# potbot_v6.net
KiCad netlist of a schematic drawn in EAGLE
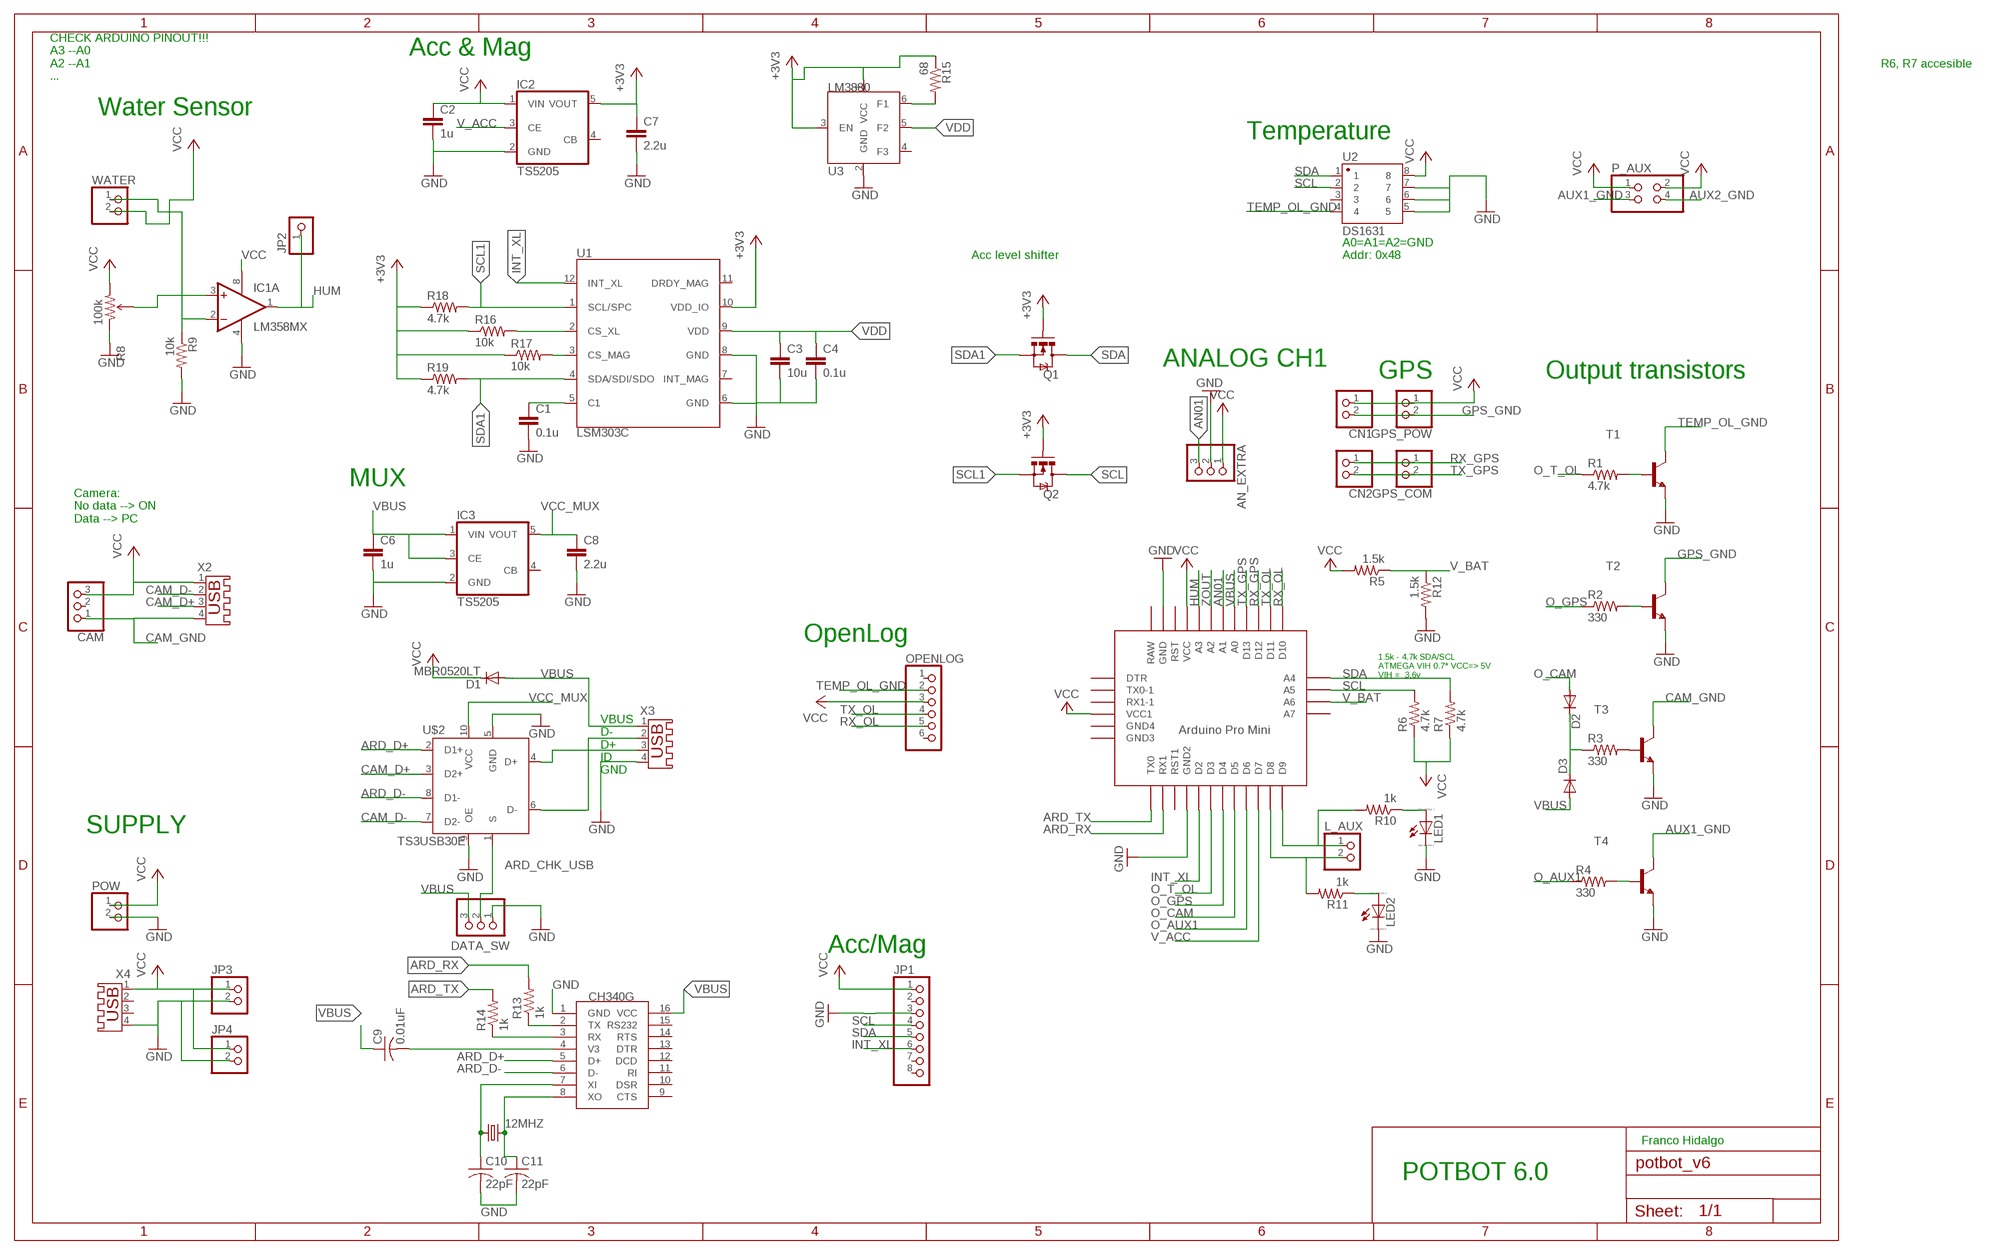
[diagram p0: schematic, sheet 1]

(export (version "E")
  (design (tool "Eeschema 10.0.6"))
  (components
    (comp (ref "12MHZ")
      (value "CRYSTALSM49")
      (footprint "eagle-import:SM49")
      (libsource (lib "eagle-import") (part "CRYSTALSM49"))
    )
    (comp (ref "AN_EXTRA")
      (value "PINHD-1X3")
      (footprint "eagle-import:1X03")
      (libsource (lib "eagle-import") (part "PINHD-1X3"))
    )
    (comp (ref "ARDUINO")
      (value "PRO-MINI-2")
      (footprint "eagle-import:PRO-MINI-2")
      (libsource (lib "eagle-import") (part "PRO-MINI-2"))
    )
    (comp (ref "C1")
      (value "0.1u")
      (footprint "eagle-import:C1206")
      (libsource (lib "eagle-import") (part "C-EUC1206"))
    )
    (comp (ref "C2")
      (value "1u")
      (footprint "eagle-import:C1206")
      (libsource (lib "eagle-import") (part "C-EUC1206"))
    )
    (comp (ref "C3")
      (value "10u")
      (footprint "eagle-import:C1206")
      (libsource (lib "eagle-import") (part "C-EUC1206"))
    )
    (comp (ref "C4")
      (value "0.1u")
      (footprint "eagle-import:C1206")
      (libsource (lib "eagle-import") (part "C-EUC1206"))
    )
    (comp (ref "C6")
      (value "1u")
      (footprint "eagle-import:C1206")
      (libsource (lib "eagle-import") (part "C-EUC1206"))
    )
    (comp (ref "C7")
      (value "2.2u")
      (footprint "eagle-import:C1206")
      (libsource (lib "eagle-import") (part "C-EUC1206"))
    )
    (comp (ref "C8")
      (value "2.2u")
      (footprint "eagle-import:C1206")
      (libsource (lib "eagle-import") (part "C-EUC1206"))
    )
    (comp (ref "C9")
      (value "0.01uF")
      (footprint "eagle-import:C1206")
      (libsource (lib "eagle-import") (part "C-USC1206"))
    )
    (comp (ref "C10")
      (value "22pF")
      (footprint "eagle-import:C1206")
      (libsource (lib "eagle-import") (part "C-USC1206"))
    )
    (comp (ref "C11")
      (value "22pF")
      (footprint "eagle-import:C1206")
      (libsource (lib "eagle-import") (part "C-USC1206"))
    )
    (comp (ref "CAM")
      (value "PINHD-1X3")
      (footprint "eagle-import:1X03")
      (libsource (lib "eagle-import") (part "pinhead_PINHD-1X3"))
    )
    (comp (ref "CN1")
      (value "JST_2PIN-THM")
      (footprint "eagle-import:JST-PH-2-THM")
      (libsource (lib "eagle-import") (part "JST_2PIN-THM"))
    )
    (comp (ref "CN2")
      (value "JST_2PIN-THM")
      (footprint "eagle-import:JST-PH-2-THM")
      (libsource (lib "eagle-import") (part "JST_2PIN-THM"))
    )
    (comp (ref "D1")
      (value "MBR0520LT")
      (footprint "eagle-import:SOD123")
      (libsource (lib "eagle-import") (part "MBR0520LT"))
    )
    (comp (ref "D2")
      (value "MBR0520LT")
      (footprint "eagle-import:SOD123")
      (libsource (lib "eagle-import") (part "MBR0520LT"))
    )
    (comp (ref "D3")
      (value "MBR0520LT")
      (footprint "eagle-import:SOD123")
      (libsource (lib "eagle-import") (part "MBR0520LT"))
    )
    (comp (ref "DATA_SW")
      (value "PINHD-1X3")
      (footprint "eagle-import:1X03")
      (libsource (lib "eagle-import") (part "pinhead_PINHD-1X3"))
    )
    (comp (ref "GPS_COM")
      (value "JST_2PIN-SMT")
      (footprint "eagle-import:JST-PH-2-SMT")
      (libsource (lib "eagle-import") (part "JST_2PIN-SMT"))
    )
    (comp (ref "GPS_POW")
      (value "JST_2PIN-SMT")
      (footprint "eagle-import:JST-PH-2-SMT")
      (libsource (lib "eagle-import") (part "JST_2PIN-SMT"))
    )
    (comp (ref "IC1")
      (value "LM358MX")
      (footprint "eagle-import:SO08")
      (libsource (lib "eagle-import") (part "LM358MX"))
    )
    (comp (ref "IC2")
      (value "TS5205")
      (footprint "eagle-import:SOT25")
      (libsource (lib "eagle-import") (part "TS5205"))
    )
    (comp (ref "IC3")
      (value "TS5205")
      (footprint "eagle-import:SOT25")
      (libsource (lib "eagle-import") (part "TS5205"))
    )
    (comp (ref "JP1")
      (value "PINHD-1X8CLEANBIG")
      (footprint "eagle-import:1X08-CLEANBIG")
      (libsource (lib "eagle-import") (part "PINHD-1X8CLEANBIG"))
    )
    (comp (ref "JP2")
      (value "PINHD-1X1")
      (footprint "eagle-import:1X01")
      (libsource (lib "eagle-import") (part "PINHD-1X1"))
    )
    (comp (ref "JP3")
      (value "PINHD-1X2")
      (footprint "eagle-import:1X02")
      (libsource (lib "eagle-import") (part "PINHD-1X2"))
    )
    (comp (ref "JP4")
      (value "PINHD-1X2")
      (footprint "eagle-import:1X02")
      (libsource (lib "eagle-import") (part "PINHD-1X2"))
    )
    (comp (ref "LED1")
      (value "LED_ELD260")
      (footprint "eagle-import:LED_LD260")
      (libsource (lib "eagle-import") (part "LED_ELD260"))
    )
    (comp (ref "LED2")
      (value "LED_ELD260")
      (footprint "eagle-import:LED_LD260")
      (libsource (lib "eagle-import") (part "LED_ELD260"))
    )
    (comp (ref "L_AUX")
      (value "PINHD-1X2")
      (footprint "eagle-import:1X02")
      (libsource (lib "eagle-import") (part "PINHD-1X2"))
    )
    (comp (ref "OPENLOG")
      (value "PINHD-1X6")
      (footprint "eagle-import:1X06")
      (libsource (lib "eagle-import") (part "PINHD-1X6"))
    )
    (comp (ref "POW")
      (value "PINHD-1X2")
      (footprint "eagle-import:1X02")
      (libsource (lib "eagle-import") (part "PINHD-1X2"))
    )
    (comp (ref "P_AUX")
      (value "PINHD-2X2")
      (footprint "eagle-import:2X02")
      (libsource (lib "eagle-import") (part "PINHD-2X2"))
    )
    (comp (ref "Q1")
      (value "MOSFET-NCHANNELAO3404A")
      (footprint "eagle-import:SOT23-3")
      (libsource (lib "eagle-import") (part "MOSFET-NCHANNELAO3404A"))
    )
    (comp (ref "Q2")
      (value "MOSFET-NCHANNELAO3404A")
      (footprint "eagle-import:SOT23-3")
      (libsource (lib "eagle-import") (part "MOSFET-NCHANNELAO3404A"))
    )
    (comp (ref "R1")
      (value "4.7k")
      (footprint "eagle-import:M1206")
      (libsource (lib "eagle-import") (part "R-US_M1206"))
    )
    (comp (ref "R2")
      (value "330")
      (footprint "eagle-import:M1206")
      (libsource (lib "eagle-import") (part "R-US_M1206"))
    )
    (comp (ref "R3")
      (value "330")
      (footprint "eagle-import:M1206")
      (libsource (lib "eagle-import") (part "R-US_M1206"))
    )
    (comp (ref "R4")
      (value "330")
      (footprint "eagle-import:M1206")
      (libsource (lib "eagle-import") (part "R-US_M1206"))
    )
    (comp (ref "R5")
      (value "1.5k")
      (footprint "eagle-import:M1206")
      (libsource (lib "eagle-import") (part "R-US_M1206"))
    )
    (comp (ref "R6")
      (value "4.7k")
      (footprint "eagle-import:M1206")
      (libsource (lib "eagle-import") (part "R-US_M1206"))
    )
    (comp (ref "R7")
      (value "4.7k")
      (footprint "eagle-import:M1206")
      (libsource (lib "eagle-import") (part "R-US_M1206"))
    )
    (comp (ref "R8")
      (value "100k")
      (footprint "eagle-import:TRIMPOT-3MM")
      (libsource (lib "eagle-import") (part "TRIMPOTRES-09285"))
    )
    (comp (ref "R9")
      (value "10k")
      (footprint "eagle-import:M1206")
      (libsource (lib "eagle-import") (part "R-US_M1206"))
    )
    (comp (ref "R10")
      (value "1k")
      (footprint "eagle-import:M1206")
      (libsource (lib "eagle-import") (part "R-US_M1206"))
    )
    (comp (ref "R11")
      (value "1k")
      (footprint "eagle-import:M1206")
      (libsource (lib "eagle-import") (part "R-US_M1206"))
    )
    (comp (ref "R12")
      (value "1.5k")
      (footprint "eagle-import:M1206")
      (libsource (lib "eagle-import") (part "R-US_M1206"))
    )
    (comp (ref "R13")
      (value "1k")
      (footprint "eagle-import:M1206")
      (libsource (lib "eagle-import") (part "R-US_M1206"))
    )
    (comp (ref "R14")
      (value "1k")
      (footprint "eagle-import:M1206")
      (libsource (lib "eagle-import") (part "R-US_M1206"))
    )
    (comp (ref "R15")
      (value "68")
      (footprint "eagle-import:M1206")
      (libsource (lib "eagle-import") (part "R-US_M1206"))
    )
    (comp (ref "R16")
      (value "10k")
      (footprint "eagle-import:M1206")
      (libsource (lib "eagle-import") (part "R-US_M1206"))
    )
    (comp (ref "R17")
      (value "10k")
      (footprint "eagle-import:M1206")
      (libsource (lib "eagle-import") (part "R-US_M1206"))
    )
    (comp (ref "R18")
      (value "4.7k")
      (footprint "eagle-import:M1206")
      (libsource (lib "eagle-import") (part "R-US_M1206"))
    )
    (comp (ref "R19")
      (value "4.7k")
      (footprint "eagle-import:M1206")
      (libsource (lib "eagle-import") (part "R-US_M1206"))
    )
    (comp (ref "T1")
      (value "BC817-25LT1-NPN-SOT23-BEC")
      (footprint "eagle-import:SOT23-BEC")
      (libsource (lib "eagle-import") (part "-NPN-SOT23-BECBC817-25LT1"))
    )
    (comp (ref "T2")
      (value "BC817-25LT1-NPN-SOT23-BEC")
      (footprint "eagle-import:SOT23-BEC")
      (libsource (lib "eagle-import") (part "-NPN-SOT23-BECBC817-25LT1"))
    )
    (comp (ref "T3")
      (value "BC817-25LT1-NPN-SOT23-BEC")
      (footprint "eagle-import:SOT23-BEC")
      (libsource (lib "eagle-import") (part "-NPN-SOT23-BECBC817-25LT1"))
    )
    (comp (ref "T4")
      (value "BC817-25LT1-NPN-SOT23-BEC")
      (footprint "eagle-import:SOT23-BEC")
      (libsource (lib "eagle-import") (part "-NPN-SOT23-BECBC817-25LT1"))
    )
    (comp (ref "U$2")
      (value "TS3USB30E")
      (footprint "eagle-import:VSSOP8")
      (libsource (lib "eagle-import") (part "TS3USB30E"))
    )
    (comp (ref "U$4")
      (value "CH340G")
      (footprint "eagle-import:SOIC16")
      (libsource (lib "eagle-import") (part "CH340G"))
    )
    (comp (ref "U1")
      (value "LSM303C")
      (footprint "eagle-import:LGA-12")
      (libsource (lib "eagle-import") (part "LSM303C"))
    )
    (comp (ref "U2")
      (value "DS1631")
      (footprint "eagle-import:SO08-UNIVERSAL")
      (libsource (lib "eagle-import") (part "GENERIC-SOIC8"))
    )
    (comp (ref "U3")
      (value "LM3880")
      (footprint "eagle-import:SOT23-6")
      (libsource (lib "eagle-import") (part "LM3880/-QI"))
    )
    (comp (ref "WATER")
      (value "PINHD-1X2")
      (footprint "eagle-import:1X02")
      (libsource (lib "eagle-import") (part "PINHD-1X2"))
    )
    (comp (ref "X2")
      (value "USB-A003")
      (footprint "eagle-import:USB-A003")
      (libsource (lib "eagle-import") (part "USB-A003"))
    )
    (comp (ref "X3")
      (value "USB-A003")
      (footprint "eagle-import:USB-A003")
      (libsource (lib "eagle-import") (part "USB-A003"))
    )
    (comp (ref "X4")
      (value "USB-A003")
      (footprint "eagle-import:USB-A003")
      (libsource (lib "eagle-import") (part "USB-A003"))
    )
  )
  (nets
    (net (code "1") (name "+3V3") (class "Default")
      (node (ref "C7") (pin "1") (pinfunction "1_1") (pintype "passive"))
      (node (ref "IC2") (pin "5") (pinfunction "VOUT_5") (pintype "passive"))
      (node (ref "Q1") (pin "1") (pinfunction "G_1") (pintype "passive"))
      (node (ref "Q2") (pin "1") (pinfunction "G_1") (pintype "passive"))
      (node (ref "R15") (pin "1") (pinfunction "1_1") (pintype "passive"))
      (node (ref "R16") (pin "1") (pinfunction "1_1") (pintype "passive"))
      (node (ref "R17") (pin "1") (pinfunction "1_1") (pintype "passive"))
      (node (ref "R18") (pin "1") (pinfunction "1_1") (pintype "passive"))
      (node (ref "R19") (pin "1") (pinfunction "1_1") (pintype "passive"))
      (node (ref "U1") (pin "10") (pinfunction "VDD_IO_10") (pintype "bidirectional"))
      (node (ref "U3") (pin "1") (pinfunction "VCC_1") (pintype "bidirectional"))
      (node (ref "U3") (pin "3") (pinfunction "EN_3") (pintype "bidirectional"))
    )
    (net (code "2") (name "/ARD_CHK_USB") (class "Default")
      (node (ref "DATA_SW") (pin "2") (pinfunction "2_2") (pintype "passive"))
      (node (ref "U$2") (pin "1") (pinfunction "S_1") (pintype "bidirectional"))
    )
    (net (code "3") (name "/ARD_D+") (class "Default")
      (node (ref "U$2") (pin "2") (pinfunction "D1+_2") (pintype "bidirectional"))
      (node (ref "U$4") (pin "5") (pinfunction "D+_5") (pintype "bidirectional"))
    )
    (net (code "4") (name "/ARD_D-") (class "Default")
      (node (ref "U$2") (pin "8") (pinfunction "D1-_8") (pintype "bidirectional"))
      (node (ref "U$4") (pin "6") (pinfunction "D-_6") (pintype "bidirectional"))
    )
    (net (code "5") (name "/AUX1_GND") (class "Default")
      (node (ref "P_AUX") (pin "3") (pinfunction "3_3") (pintype "passive"))
      (node (ref "T4") (pin "C") (pinfunction "C_C") (pintype "passive"))
    )
    (net (code "6") (name "/AUX2_GND") (class "Default")
      (node (ref "P_AUX") (pin "4") (pinfunction "4_4") (pintype "passive"))
    )
    (net (code "7") (name "/CAM_D+") (class "Default")
      (node (ref "U$2") (pin "3") (pinfunction "D2+_3") (pintype "bidirectional"))
      (node (ref "X2") (pin "3") (pinfunction "3_3") (pintype "passive"))
    )
    (net (code "8") (name "/CAM_D-") (class "Default")
      (node (ref "U$2") (pin "7") (pinfunction "D2-_7") (pintype "bidirectional"))
      (node (ref "X2") (pin "2") (pinfunction "2_2") (pintype "passive"))
    )
    (net (code "9") (name "/CAM_GND") (class "Default")
      (node (ref "CAM") (pin "1") (pinfunction "1_1") (pintype "passive"))
      (node (ref "T3") (pin "C") (pinfunction "C_C") (pintype "passive"))
      (node (ref "X2") (pin "4") (pinfunction "4_4") (pintype "passive"))
    )
    (net (code "10") (name "/GPS_GND") (class "Default")
      (node (ref "CN1") (pin "2") (pinfunction "1_2") (pintype "passive"))
      (node (ref "GPS_POW") (pin "2") (pinfunction "1_2") (pintype "passive"))
      (node (ref "T2") (pin "C") (pinfunction "C_C") (pintype "passive"))
    )
    (net (code "11") (name "/HUM") (class "Default")
      (node (ref "ARDUINO") (pin "A3") (pinfunction "A3_A3") (pintype "bidirectional"))
      (node (ref "IC1") (pin "1") (pinfunction "OUT_1") (pintype "output"))
      (node (ref "JP2") (pin "1") (pinfunction "1_1") (pintype "passive"))
    )
    (net (code "12") (name "/O_AUX1") (class "Default")
      (node (ref "ARDUINO") (pin "D6") (pinfunction "D6_D6") (pintype "bidirectional"))
      (node (ref "R4") (pin "1") (pinfunction "1_1") (pintype "passive"))
    )
    (net (code "13") (name "/O_CAM") (class "Default")
      (node (ref "ARDUINO") (pin "D5") (pinfunction "D5_D5") (pintype "bidirectional"))
      (node (ref "D2") (pin "A") (pinfunction "A_A") (pintype "passive"))
    )
    (net (code "14") (name "/O_GPS") (class "Default")
      (node (ref "ARDUINO") (pin "D4") (pinfunction "D4_D4") (pintype "bidirectional"))
      (node (ref "R2") (pin "1") (pinfunction "1_1") (pintype "passive"))
    )
    (net (code "15") (name "/O_T_OL") (class "Default")
      (node (ref "ARDUINO") (pin "D3") (pinfunction "D3_D3") (pintype "bidirectional"))
      (node (ref "R1") (pin "1") (pinfunction "1_1") (pintype "passive"))
    )
    (net (code "16") (name "/RX_GPS") (class "Default")
      (node (ref "ARDUINO") (pin "D12") (pinfunction "D12_D12") (pintype "bidirectional"))
      (node (ref "CN2") (pin "1") (pinfunction "2_1") (pintype "passive"))
      (node (ref "GPS_COM") (pin "1") (pinfunction "2_1") (pintype "passive"))
    )
    (net (code "17") (name "/RX_OL") (class "Default")
      (node (ref "ARDUINO") (pin "D10") (pinfunction "D10_D10") (pintype "bidirectional"))
      (node (ref "OPENLOG") (pin "5") (pinfunction "5_5") (pintype "passive"))
    )
    (net (code "18") (name "/TEMP_OL_GND") (class "Default")
      (node (ref "OPENLOG") (pin "2") (pinfunction "2_2") (pintype "passive"))
      (node (ref "T1") (pin "C") (pinfunction "C_C") (pintype "passive"))
      (node (ref "U2") (pin "4") (pinfunction "4_4") (pintype "bidirectional"))
    )
    (net (code "19") (name "/TX_GPS") (class "Default")
      (node (ref "ARDUINO") (pin "D13") (pinfunction "D13_D13") (pintype "bidirectional"))
      (node (ref "CN2") (pin "2") (pinfunction "1_2") (pintype "passive"))
      (node (ref "GPS_COM") (pin "2") (pinfunction "1_2") (pintype "passive"))
    )
    (net (code "20") (name "/TX_OL") (class "Default")
      (node (ref "ARDUINO") (pin "D11") (pinfunction "D11_D11") (pintype "bidirectional"))
      (node (ref "OPENLOG") (pin "4") (pinfunction "4_4") (pintype "passive"))
    )
    (net (code "21") (name "/VCC_MUX") (class "Default")
      (node (ref "C8") (pin "1") (pinfunction "1_1") (pintype "passive"))
      (node (ref "IC3") (pin "5") (pinfunction "VOUT_5") (pintype "passive"))
      (node (ref "U$2") (pin "10") (pinfunction "VCC_10") (pintype "bidirectional"))
    )
    (net (code "22") (name "/V_ACC") (class "Default")
      (node (ref "ARDUINO") (pin "D7") (pinfunction "D7_D7") (pintype "bidirectional"))
      (node (ref "IC2") (pin "3") (pinfunction "CE_3") (pintype "input"))
    )
    (net (code "23") (name "/V_BAT") (class "Default")
      (node (ref "ARDUINO") (pin "A6") (pinfunction "A6_A6") (pintype "bidirectional"))
      (node (ref "R12") (pin "1") (pinfunction "1_1") (pintype "passive"))
      (node (ref "R5") (pin "1") (pinfunction "1_1") (pintype "passive"))
    )
    (net (code "24") (name "/ZOUT") (class "Default")
      (node (ref "ARDUINO") (pin "A2") (pinfunction "A2_A2") (pintype "bidirectional"))
    )
    (net (code "25") (name "AN01") (class "Default")
      (node (ref "AN_EXTRA") (pin "3") (pinfunction "3_3") (pintype "passive"))
      (node (ref "ARDUINO") (pin "A1") (pinfunction "A1_A1") (pintype "bidirectional"))
    )
    (net (code "26") (name "ARD_RX") (class "Default")
      (node (ref "ARDUINO") (pin "RX1") (pinfunction "RX1_RX1") (pintype "bidirectional"))
      (node (ref "R13") (pin "2") (pinfunction "2_2") (pintype "passive"))
    )
    (net (code "27") (name "ARD_TX") (class "Default")
      (node (ref "ARDUINO") (pin "TX0") (pinfunction "TX0_TX0") (pintype "bidirectional"))
      (node (ref "R14") (pin "2") (pinfunction "2_2") (pintype "passive"))
    )
    (net (code "28") (name "GND") (class "Default")
      (node (ref "AN_EXTRA") (pin "2") (pinfunction "2_2") (pintype "passive"))
      (node (ref "ARDUINO") (pin "GND") (pinfunction "GND_GND") (pintype "bidirectional"))
      (node (ref "ARDUINO") (pin "GND1") (pinfunction "GND2_GND1") (pintype "bidirectional"))
      (node (ref "C1") (pin "2") (pinfunction "2_2") (pintype "passive"))
      (node (ref "C10") (pin "2") (pinfunction "2_2") (pintype "passive"))
      (node (ref "C11") (pin "2") (pinfunction "2_2") (pintype "passive"))
      (node (ref "C2") (pin "2") (pinfunction "2_2") (pintype "passive"))
      (node (ref "C3") (pin "2") (pinfunction "2_2") (pintype "passive"))
      (node (ref "C4") (pin "2") (pinfunction "2_2") (pintype "passive"))
      (node (ref "C6") (pin "2") (pinfunction "2_2") (pintype "passive"))
      (node (ref "C7") (pin "2") (pinfunction "2_2") (pintype "passive"))
      (node (ref "C8") (pin "2") (pinfunction "2_2") (pintype "passive"))
      (node (ref "DATA_SW") (pin "1") (pinfunction "1_1") (pintype "passive"))
      (node (ref "IC1") (pin "4") (pinfunction "V-_4") (pintype "power_in"))
      (node (ref "IC2") (pin "2") (pinfunction "GND_2") (pintype "passive"))
      (node (ref "IC3") (pin "2") (pinfunction "GND_2") (pintype "passive"))
      (node (ref "JP1") (pin "3") (pinfunction "3_3") (pintype "passive"))
      (node (ref "JP3") (pin "2") (pinfunction "2_2") (pintype "passive"))
      (node (ref "JP4") (pin "2") (pinfunction "2_2") (pintype "passive"))
      (node (ref "LED1") (pin "K") (pinfunction "C_K") (pintype "passive"))
      (node (ref "LED2") (pin "K") (pinfunction "C_K") (pintype "passive"))
      (node (ref "POW") (pin "2") (pinfunction "2_2") (pintype "passive"))
      (node (ref "R12") (pin "2") (pinfunction "2_2") (pintype "passive"))
      (node (ref "R8") (pin "1") (pinfunction "CCW_1") (pintype "passive"))
      (node (ref "R9") (pin "2") (pinfunction "2_2") (pintype "passive"))
      (node (ref "T1") (pin "E") (pinfunction "E_E") (pintype "passive"))
      (node (ref "T2") (pin "E") (pinfunction "E_E") (pintype "passive"))
      (node (ref "T3") (pin "E") (pinfunction "E_E") (pintype "passive"))
      (node (ref "T4") (pin "E") (pinfunction "E_E") (pintype "passive"))
      (node (ref "U$2") (pin "5") (pinfunction "GND_5") (pintype "bidirectional"))
      (node (ref "U$2") (pin "9") (pinfunction "OE_9") (pintype "bidirectional"))
      (node (ref "U$4") (pin "1") (pinfunction "GND_1") (pintype "bidirectional"))
      (node (ref "U1") (pin "6") (pinfunction "GND_6") (pintype "bidirectional"))
      (node (ref "U1") (pin "8") (pinfunction "GND_8") (pintype "bidirectional"))
      (node (ref "U2") (pin "5") (pinfunction "5_5") (pintype "bidirectional"))
      (node (ref "U2") (pin "6") (pinfunction "6_6") (pintype "bidirectional"))
      (node (ref "U2") (pin "7") (pinfunction "7_7") (pintype "bidirectional"))
      (node (ref "U3") (pin "2") (pinfunction "GND_2") (pintype "bidirectional"))
      (node (ref "X3") (pin "4") (pinfunction "4_4") (pintype "passive"))
      (node (ref "X4") (pin "4") (pinfunction "4_4") (pintype "passive"))
    )
    (net (code "29") (name "INT_XL") (class "Default")
      (node (ref "ARDUINO") (pin "D2") (pinfunction "D2_D2") (pintype "bidirectional"))
      (node (ref "JP1") (pin "6") (pinfunction "6_6") (pintype "passive"))
      (node (ref "U1") (pin "12") (pinfunction "INT_XL_12") (pintype "bidirectional"))
    )
    (net (code "30") (name "Net-(ARDUINO-PadD8)") (class "Default")
      (node (ref "ARDUINO") (pin "D8") (pinfunction "D8_D8") (pintype "bidirectional"))
      (node (ref "L_AUX") (pin "2") (pinfunction "2_2") (pintype "passive"))
      (node (ref "R11") (pin "2") (pinfunction "2_2") (pintype "passive"))
    )
    (net (code "31") (name "Net-(ARDUINO-PadD9)") (class "Default")
      (node (ref "ARDUINO") (pin "D9") (pinfunction "D9_D9") (pintype "bidirectional"))
      (node (ref "L_AUX") (pin "1") (pinfunction "1_1") (pintype "passive"))
      (node (ref "R10") (pin "2") (pinfunction "2_2") (pintype "passive"))
    )
    (net (code "32") (name "Net-(D2-PadC)") (class "Default")
      (node (ref "D2") (pin "C") (pinfunction "C_C") (pintype "passive"))
      (node (ref "D3") (pin "C") (pinfunction "C_C") (pintype "passive"))
      (node (ref "R3") (pin "1") (pinfunction "1_1") (pintype "passive"))
    )
    (net (code "33") (name "Net-(IC1A-+IN)") (class "Default")
      (node (ref "IC1") (pin "3") (pinfunction "+IN_3") (pintype "input"))
      (node (ref "R8") (pin "2") (pinfunction "WIPER_2") (pintype "passive"))
    )
    (net (code "34") (name "Net-(IC1A--IN)") (class "Default")
      (node (ref "IC1") (pin "2") (pinfunction "-IN_2") (pintype "input"))
      (node (ref "R9") (pin "1") (pinfunction "1_1") (pintype "passive"))
      (node (ref "WATER") (pin "1") (pinfunction "1_1") (pintype "passive"))
    )
    (net (code "35") (name "Net-(LED1-PadA)") (class "Default")
      (node (ref "LED1") (pin "A") (pinfunction "A_A") (pintype "passive"))
      (node (ref "R10") (pin "1") (pinfunction "1_1") (pintype "passive"))
    )
    (net (code "36") (name "Net-(LED2-PadA)") (class "Default")
      (node (ref "LED2") (pin "A") (pinfunction "A_A") (pintype "passive"))
      (node (ref "R11") (pin "1") (pinfunction "1_1") (pintype "passive"))
    )
    (net (code "37") (name "Net-(R1-Pad2)") (class "Default")
      (node (ref "R1") (pin "2") (pinfunction "2_2") (pintype "passive"))
      (node (ref "T1") (pin "B") (pinfunction "B_B") (pintype "passive"))
    )
    (net (code "38") (name "Net-(R2-Pad2)") (class "Default")
      (node (ref "R2") (pin "2") (pinfunction "2_2") (pintype "passive"))
      (node (ref "T2") (pin "B") (pinfunction "B_B") (pintype "passive"))
    )
    (net (code "39") (name "Net-(R3-Pad2)") (class "Default")
      (node (ref "R3") (pin "2") (pinfunction "2_2") (pintype "passive"))
      (node (ref "T3") (pin "B") (pinfunction "B_B") (pintype "passive"))
    )
    (net (code "40") (name "Net-(R4-Pad2)") (class "Default")
      (node (ref "R4") (pin "2") (pinfunction "2_2") (pintype "passive"))
      (node (ref "T4") (pin "B") (pinfunction "B_B") (pintype "passive"))
    )
    (net (code "41") (name "Net-(U$2-D+)") (class "Default")
      (node (ref "U$2") (pin "4") (pinfunction "D+_4") (pintype "bidirectional"))
      (node (ref "X3") (pin "3") (pinfunction "3_3") (pintype "passive"))
    )
    (net (code "42") (name "Net-(U$2-D-)") (class "Default")
      (node (ref "U$2") (pin "6") (pinfunction "D-_6") (pintype "bidirectional"))
      (node (ref "X3") (pin "2") (pinfunction "2_2") (pintype "passive"))
    )
    (net (code "43") (name "Net-(U$4-RX)") (class "Default")
      (node (ref "R14") (pin "1") (pinfunction "1_1") (pintype "passive"))
      (node (ref "U$4") (pin "3") (pinfunction "RX_3") (pintype "bidirectional"))
    )
    (net (code "44") (name "Net-(U$4-TX)") (class "Default")
      (node (ref "R13") (pin "1") (pinfunction "1_1") (pintype "passive"))
      (node (ref "U$4") (pin "2") (pinfunction "TX_2") (pintype "bidirectional"))
    )
    (net (code "45") (name "Net-(U$4-V3)") (class "Default")
      (node (ref "C9") (pin "2") (pinfunction "2_2") (pintype "passive"))
      (node (ref "U$4") (pin "4") (pinfunction "V3_4") (pintype "bidirectional"))
    )
    (net (code "46") (name "Net-(U$4-XI)") (class "Default")
      (node (ref "12MHZ") (pin "1") (pinfunction "1_1") (pintype "passive"))
      (node (ref "C10") (pin "1") (pinfunction "1_1") (pintype "passive"))
      (node (ref "U$4") (pin "7") (pinfunction "XI_7") (pintype "bidirectional"))
    )
    (net (code "47") (name "Net-(U$4-XO)") (class "Default")
      (node (ref "12MHZ") (pin "2") (pinfunction "2_2") (pintype "passive"))
      (node (ref "C11") (pin "1") (pinfunction "1_1") (pintype "passive"))
      (node (ref "U$4") (pin "8") (pinfunction "XO_8") (pintype "bidirectional"))
    )
    (net (code "48") (name "Net-(U1-C1)") (class "Default")
      (node (ref "C1") (pin "1") (pinfunction "1_1") (pintype "passive"))
      (node (ref "U1") (pin "5") (pinfunction "C1_5") (pintype "bidirectional"))
    )
    (net (code "49") (name "Net-(U1-CS_MAG)") (class "Default")
      (node (ref "R17") (pin "2") (pinfunction "2_2") (pintype "passive"))
      (node (ref "U1") (pin "3") (pinfunction "CS_MAG_3") (pintype "bidirectional"))
    )
    (net (code "50") (name "Net-(U1-CS_XL)") (class "Default")
      (node (ref "R16") (pin "2") (pinfunction "2_2") (pintype "passive"))
      (node (ref "U1") (pin "2") (pinfunction "CS_XL_2") (pintype "bidirectional"))
    )
    (net (code "51") (name "Net-(U3-F1)") (class "Default")
      (node (ref "R15") (pin "2") (pinfunction "2_2") (pintype "passive"))
      (node (ref "U3") (pin "6") (pinfunction "F1_6") (pintype "bidirectional"))
    )
    (net (code "52") (name "SCL") (class "Default")
      (node (ref "ARDUINO") (pin "A5") (pinfunction "A5_A5") (pintype "bidirectional"))
      (node (ref "JP1") (pin "4") (pinfunction "4_4") (pintype "passive"))
      (node (ref "Q2") (pin "3") (pinfunction "D_3") (pintype "passive"))
      (node (ref "R6") (pin "2") (pinfunction "2_2") (pintype "passive"))
      (node (ref "U2") (pin "2") (pinfunction "2_2") (pintype "bidirectional"))
    )
    (net (code "53") (name "SCL1") (class "Default")
      (node (ref "Q2") (pin "2") (pinfunction "S_2") (pintype "passive"))
      (node (ref "R18") (pin "2") (pinfunction "2_2") (pintype "passive"))
      (node (ref "U1") (pin "1") (pinfunction "SCL/SPC_1") (pintype "bidirectional"))
    )
    (net (code "54") (name "SDA") (class "Default")
      (node (ref "ARDUINO") (pin "A4") (pinfunction "A4_A4") (pintype "bidirectional"))
      (node (ref "JP1") (pin "5") (pinfunction "5_5") (pintype "passive"))
      (node (ref "Q1") (pin "3") (pinfunction "D_3") (pintype "passive"))
      (node (ref "R7") (pin "2") (pinfunction "2_2") (pintype "passive"))
      (node (ref "U2") (pin "1") (pinfunction "1_1") (pintype "bidirectional"))
    )
    (net (code "55") (name "SDA1") (class "Default")
      (node (ref "Q1") (pin "2") (pinfunction "S_2") (pintype "passive"))
      (node (ref "R19") (pin "2") (pinfunction "2_2") (pintype "passive"))
      (node (ref "U1") (pin "4") (pinfunction "SDA/SDI/SDO_4") (pintype "bidirectional"))
    )
    (net (code "56") (name "VBUS") (class "Default")
      (node (ref "ARDUINO") (pin "A0") (pinfunction "A0_A0") (pintype "bidirectional"))
      (node (ref "C6") (pin "1") (pinfunction "1_1") (pintype "passive"))
      (node (ref "C9") (pin "1") (pinfunction "1_1") (pintype "passive"))
      (node (ref "D1") (pin "A") (pinfunction "A_A") (pintype "passive"))
      (node (ref "D3") (pin "A") (pinfunction "A_A") (pintype "passive"))
      (node (ref "DATA_SW") (pin "3") (pinfunction "3_3") (pintype "passive"))
      (node (ref "IC3") (pin "1") (pinfunction "VIN_1") (pintype "input"))
      (node (ref "IC3") (pin "3") (pinfunction "CE_3") (pintype "input"))
      (node (ref "U$4") (pin "16") (pinfunction "VCC_16") (pintype "bidirectional"))
      (node (ref "X3") (pin "1") (pinfunction "1_1") (pintype "passive"))
    )
    (net (code "57") (name "VCC") (class "Default")
      (node (ref "AN_EXTRA") (pin "1") (pinfunction "1_1") (pintype "passive"))
      (node (ref "ARDUINO") (pin "VCC") (pinfunction "VCC_VCC") (pintype "bidirectional"))
      (node (ref "ARDUINO") (pin "VCC1") (pinfunction "VCC1_VCC1") (pintype "bidirectional"))
      (node (ref "C2") (pin "1") (pinfunction "1_1") (pintype "passive"))
      (node (ref "CAM") (pin "3") (pinfunction "3_3") (pintype "passive"))
      (node (ref "CN1") (pin "1") (pinfunction "2_1") (pintype "passive"))
      (node (ref "D1") (pin "C") (pinfunction "C_C") (pintype "passive"))
      (node (ref "GPS_POW") (pin "1") (pinfunction "2_1") (pintype "passive"))
      (node (ref "IC1") (pin "8") (pinfunction "V+_8") (pintype "power_in"))
      (node (ref "IC2") (pin "1") (pinfunction "VIN_1") (pintype "input"))
      (node (ref "JP1") (pin "1") (pinfunction "1_1") (pintype "passive"))
      (node (ref "JP3") (pin "1") (pinfunction "1_1") (pintype "passive"))
      (node (ref "JP4") (pin "1") (pinfunction "1_1") (pintype "passive"))
      (node (ref "OPENLOG") (pin "3") (pinfunction "3_3") (pintype "passive"))
      (node (ref "POW") (pin "1") (pinfunction "1_1") (pintype "passive"))
      (node (ref "P_AUX") (pin "1") (pinfunction "1_1") (pintype "passive"))
      (node (ref "P_AUX") (pin "2") (pinfunction "2_2") (pintype "passive"))
      (node (ref "R5") (pin "2") (pinfunction "2_2") (pintype "passive"))
      (node (ref "R6") (pin "1") (pinfunction "1_1") (pintype "passive"))
      (node (ref "R7") (pin "1") (pinfunction "1_1") (pintype "passive"))
      (node (ref "R8") (pin "3") (pinfunction "CW_3") (pintype "passive"))
      (node (ref "U2") (pin "8") (pinfunction "8_8") (pintype "bidirectional"))
      (node (ref "WATER") (pin "2") (pinfunction "2_2") (pintype "passive"))
      (node (ref "X2") (pin "1") (pinfunction "1_1") (pintype "passive"))
      (node (ref "X4") (pin "1") (pinfunction "1_1") (pintype "passive"))
    )
    (net (code "58") (name "VDD") (class "Default")
      (node (ref "C3") (pin "1") (pinfunction "1_1") (pintype "passive"))
      (node (ref "C4") (pin "1") (pinfunction "1_1") (pintype "passive"))
      (node (ref "U1") (pin "9") (pinfunction "VDD_9") (pintype "bidirectional"))
      (node (ref "U3") (pin "5") (pinfunction "F2_5") (pintype "bidirectional"))
    )
    (net (code "59") (name "unconnected-(ARDUINO-GND3-PadGND2)") (class "Default")
      (node (ref "ARDUINO") (pin "GND2") (pinfunction "GND3_GND2") (pintype "bidirectional"))
    )
    (net (code "60") (name "unconnected-(ARDUINO-GND4-PadGND3)") (class "Default")
      (node (ref "ARDUINO") (pin "GND3") (pinfunction "GND4_GND3") (pintype "bidirectional"))
    )
    (net (code "61") (name "unconnected-(ARDUINO-PadA7)") (class "Default")
      (node (ref "ARDUINO") (pin "A7") (pinfunction "A7_A7") (pintype "bidirectional"))
    )
    (net (code "62") (name "unconnected-(ARDUINO-PadDTR)") (class "Default")
      (node (ref "ARDUINO") (pin "DTR") (pinfunction "DTR_DTR") (pintype "bidirectional"))
    )
    (net (code "63") (name "unconnected-(ARDUINO-PadRAW)") (class "Default")
      (node (ref "ARDUINO") (pin "RAW") (pinfunction "RAW_RAW") (pintype "bidirectional"))
    )
    (net (code "64") (name "unconnected-(ARDUINO-PadRST)") (class "Default")
      (node (ref "ARDUINO") (pin "RST") (pinfunction "RST_RST") (pintype "bidirectional"))
    )
    (net (code "65") (name "unconnected-(ARDUINO-PadRST1)") (class "Default")
      (node (ref "ARDUINO") (pin "RST1") (pinfunction "RST1_RST1") (pintype "bidirectional"))
    )
    (net (code "66") (name "unconnected-(ARDUINO-PadRX1-1)") (class "Default")
      (node (ref "ARDUINO") (pin "RX1-1") (pinfunction "RX1-1_RX1-1") (pintype "bidirectional"))
    )
    (net (code "67") (name "unconnected-(ARDUINO-PadTX0-1)") (class "Default")
      (node (ref "ARDUINO") (pin "TX0-1") (pinfunction "TX0-1_TX0-1") (pintype "bidirectional"))
    )
    (net (code "68") (name "unconnected-(CAM-Pad2)") (class "Default")
      (node (ref "CAM") (pin "2") (pinfunction "2_2") (pintype "passive"))
    )
    (net (code "69") (name "unconnected-(IC2-CB-Pad4)") (class "Default")
      (node (ref "IC2") (pin "4") (pinfunction "CB_4") (pintype "input"))
    )
    (net (code "70") (name "unconnected-(IC3-CB-Pad4)") (class "Default")
      (node (ref "IC3") (pin "4") (pinfunction "CB_4") (pintype "input"))
    )
    (net (code "71") (name "unconnected-(JP1-Pad2)") (class "Default")
      (node (ref "JP1") (pin "2") (pinfunction "2_2") (pintype "passive"))
    )
    (net (code "72") (name "unconnected-(JP1-Pad7)") (class "Default")
      (node (ref "JP1") (pin "7") (pinfunction "7_7") (pintype "passive"))
    )
    (net (code "73") (name "unconnected-(JP1-Pad8)") (class "Default")
      (node (ref "JP1") (pin "8") (pinfunction "8_8") (pintype "passive"))
    )
    (net (code "74") (name "unconnected-(OPENLOG-Pad1)") (class "Default")
      (node (ref "OPENLOG") (pin "1") (pinfunction "1_1") (pintype "passive"))
    )
    (net (code "75") (name "unconnected-(OPENLOG-Pad6)") (class "Default")
      (node (ref "OPENLOG") (pin "6") (pinfunction "6_6") (pintype "passive"))
    )
    (net (code "76") (name "unconnected-(U$4-CTS-Pad9)") (class "Default")
      (node (ref "U$4") (pin "9") (pinfunction "CTS_9") (pintype "bidirectional"))
    )
    (net (code "77") (name "unconnected-(U$4-DCD-Pad12)") (class "Default")
      (node (ref "U$4") (pin "12") (pinfunction "DCD_12") (pintype "bidirectional"))
    )
    (net (code "78") (name "unconnected-(U$4-DSR-Pad10)") (class "Default")
      (node (ref "U$4") (pin "10") (pinfunction "DSR_10") (pintype "bidirectional"))
    )
    (net (code "79") (name "unconnected-(U$4-DTR-Pad13)") (class "Default")
      (node (ref "U$4") (pin "13") (pinfunction "DTR_13") (pintype "bidirectional"))
    )
    (net (code "80") (name "unconnected-(U$4-RI-Pad11)") (class "Default")
      (node (ref "U$4") (pin "11") (pinfunction "RI_11") (pintype "bidirectional"))
    )
    (net (code "81") (name "unconnected-(U$4-RS232-Pad15)") (class "Default")
      (node (ref "U$4") (pin "15") (pinfunction "RS232_15") (pintype "bidirectional"))
    )
    (net (code "82") (name "unconnected-(U$4-RTS-Pad14)") (class "Default")
      (node (ref "U$4") (pin "14") (pinfunction "RTS_14") (pintype "bidirectional"))
    )
    (net (code "83") (name "unconnected-(U1-DRDY_MAG-Pad11)") (class "Default")
      (node (ref "U1") (pin "11") (pinfunction "DRDY_MAG_11") (pintype "bidirectional"))
    )
    (net (code "84") (name "unconnected-(U1-INT_MAG-Pad7)") (class "Default")
      (node (ref "U1") (pin "7") (pinfunction "INT_MAG_7") (pintype "bidirectional"))
    )
    (net (code "85") (name "unconnected-(U2-Pad3)") (class "Default")
      (node (ref "U2") (pin "3") (pinfunction "3_3") (pintype "bidirectional"))
    )
    (net (code "86") (name "unconnected-(U3-F3-Pad4)") (class "Default")
      (node (ref "U3") (pin "4") (pinfunction "F3_4") (pintype "bidirectional"))
    )
    (net (code "87") (name "unconnected-(X4-Pad2)") (class "Default")
      (node (ref "X4") (pin "2") (pinfunction "2_2") (pintype "passive"))
    )
    (net (code "88") (name "unconnected-(X4-Pad3)") (class "Default")
      (node (ref "X4") (pin "3") (pinfunction "3_3") (pintype "passive"))
    )
  )
)
